# Akustikk_forsterkerkrets.net
KiCad netlist of a schematic drawn in Altium Designer
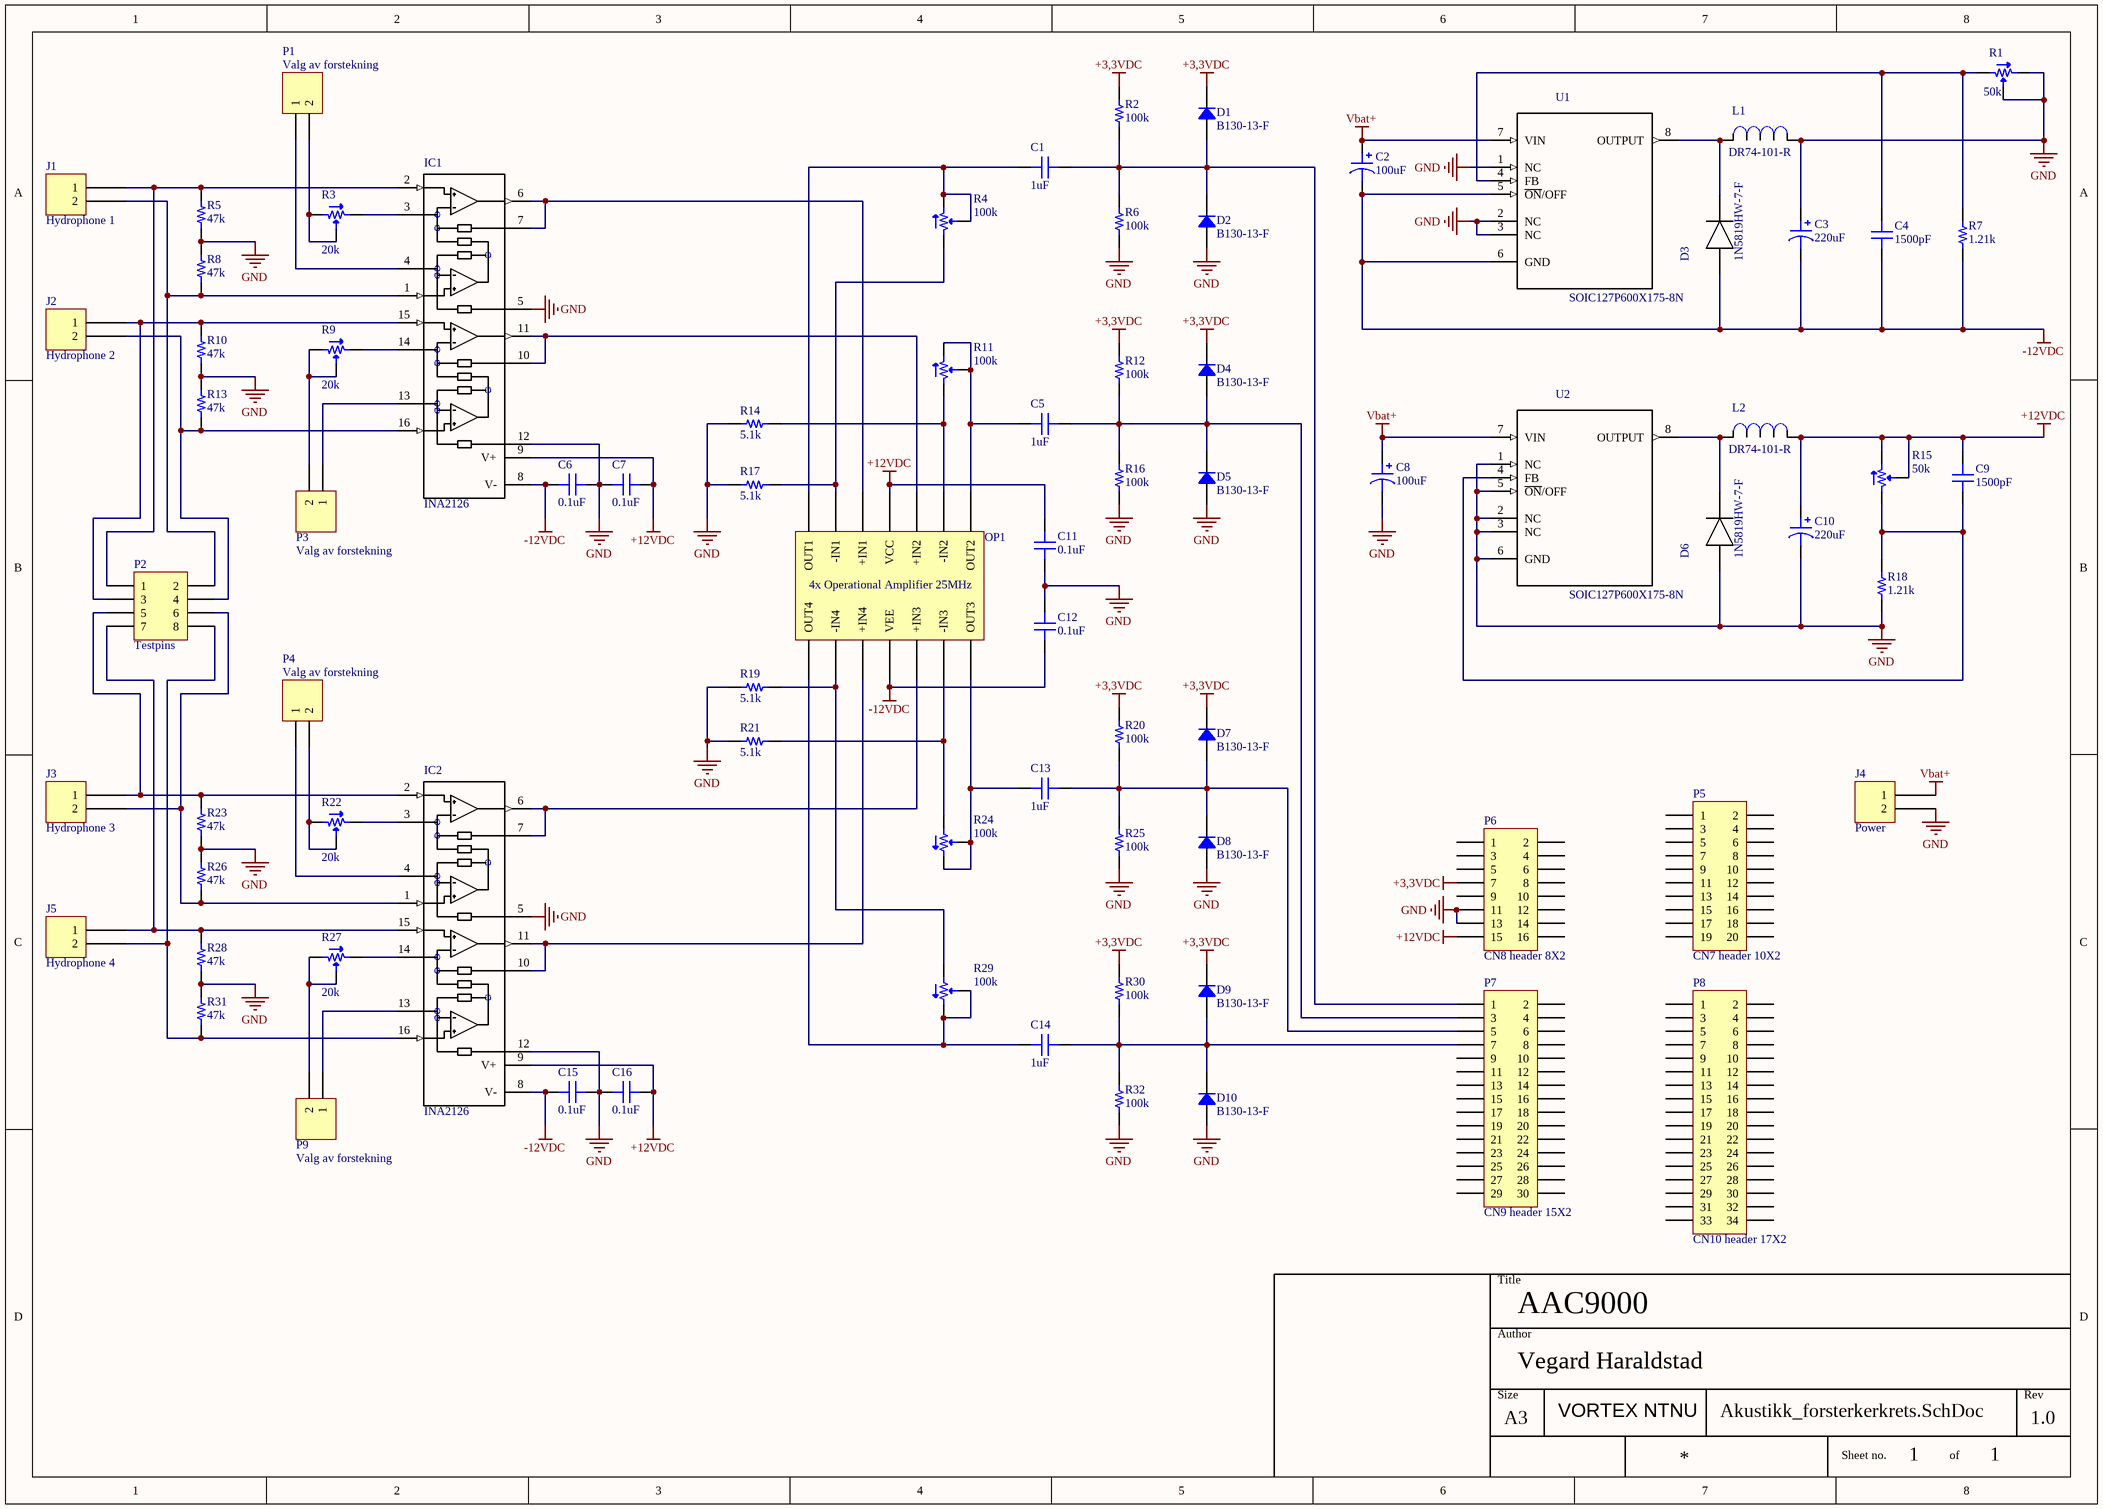
[diagram p0: Akustikk_forsterkerkrets.SchDoc]

(export (version "E")
  (design (tool "Eeschema 10.0.6"))
  (components
    (comp (ref "C1")
      (value "1uF")
      (footprint "CAP 0805/2012")
      (description "CAP CER 1UF 25V X7R 0805")
      (fields (field (name "PART NUMBER") "C0805C105J3RACTU") (field (name "MANUFACTURER") "Kemet"))
      (libsource (lib "Celestial Library Database") (part "Capacitor"))
    )
    (comp (ref "C2")
      (value "100uF")
      (footprint "CAP ALUM 10.3MM")
      (description "CAP ALUM 100UF 20% 50V SMD")
      (fields
        (field (name "PART NUMBER") "EEE-FC1H101P")
        (field (name "MANUFACTURER") "Panasonic Electronic Components")
      )
      (libsource (lib "Celestial Library Database") (part "Polarised Capacitor"))
    )
    (comp (ref "C3")
      (value "220uF")
      (footprint "CAP ALUM 6.6MM")
      (description "CAP ALUM 220UF 20% 25V SMD")
      (fields
        (field (name "PART NUMBER") "EEE-FTE221XAP")
        (field (name "MANUFACTURER") "Panasonic Electronic Components")
      )
      (libsource (lib "Celestial Library Database") (part "Polarised Capacitor"))
    )
    (comp (ref "C4")
      (value "1500pF")
      (footprint "CAP 0805/2012")
      (description "CAP CER 1500PF 50V C0G 0805")
      (fields
        (field (name "PART NUMBER") "C2012C0G1H152J060AA")
        (field (name "MANUFACTURER") "TDK Corporation")
      )
      (libsource (lib "Celestial Library Database") (part "Capacitor"))
    )
    (comp (ref "C5")
      (value "1uF")
      (footprint "CAP 0805/2012")
      (description "CAP CER 1UF 25V X7R 0805")
      (fields (field (name "PART NUMBER") "C0805C105J3RACTU") (field (name "MANUFACTURER") "Kemet"))
      (libsource (lib "Celestial Library Database") (part "Capacitor"))
    )
    (comp (ref "C6")
      (value "0.1uF")
      (footprint "CAP 0805/2012")
      (description "CAP CER 0.1UF 25V X7R 0805")
      (fields
        (field (name "PART NUMBER") "CL21B104KACNNNC")
        (field (name "MANUFACTURER") "Samsung Electro-Mechanics America, Inc.")
      )
      (libsource (lib "Celestial Library Database") (part "Capacitor"))
    )
    (comp (ref "C7")
      (value "0.1uF")
      (footprint "CAP 0805/2012")
      (description "CAP CER 0.1UF 25V X7R 0805")
      (fields
        (field (name "PART NUMBER") "CL21B104KACNNNC")
        (field (name "MANUFACTURER") "Samsung Electro-Mechanics America, Inc.")
      )
      (libsource (lib "Celestial Library Database") (part "Capacitor"))
    )
    (comp (ref "C8")
      (value "100uF")
      (footprint "CAP ALUM 10.3MM")
      (description "CAP ALUM 100UF 20% 50V SMD")
      (fields
        (field (name "PART NUMBER") "EEE-FC1H101P")
        (field (name "MANUFACTURER") "Panasonic Electronic Components")
      )
      (libsource (lib "Celestial Library Database") (part "Polarised Capacitor"))
    )
    (comp (ref "C9")
      (value "1500pF")
      (footprint "CAP 0805/2012")
      (description "CAP CER 1500PF 50V C0G 0805")
      (fields
        (field (name "PART NUMBER") "C2012C0G1H152J060AA")
        (field (name "MANUFACTURER") "TDK Corporation")
      )
      (libsource (lib "Celestial Library Database") (part "Capacitor"))
    )
    (comp (ref "C10")
      (value "220uF")
      (footprint "CAP ALUM 6.6MM")
      (description "CAP ALUM 220UF 20% 25V SMD")
      (fields
        (field (name "PART NUMBER") "EEE-FTE221XAP")
        (field (name "MANUFACTURER") "Panasonic Electronic Components")
      )
      (libsource (lib "Celestial Library Database") (part "Polarised Capacitor"))
    )
    (comp (ref "C11")
      (value "0.1uF")
      (footprint "CAP 0805/2012")
      (description "CAP CER 0.1UF 25V X7R 0805")
      (fields
        (field (name "PART NUMBER") "CL21B104KACNNNC")
        (field (name "MANUFACTURER") "Samsung Electro-Mechanics America, Inc.")
      )
      (libsource (lib "Celestial Library Database") (part "Capacitor"))
    )
    (comp (ref "C12")
      (value "0.1uF")
      (footprint "CAP 0805/2012")
      (description "CAP CER 0.1UF 25V X7R 0805")
      (fields
        (field (name "PART NUMBER") "CL21B104KACNNNC")
        (field (name "MANUFACTURER") "Samsung Electro-Mechanics America, Inc.")
      )
      (libsource (lib "Celestial Library Database") (part "Capacitor"))
    )
    (comp (ref "C13")
      (value "1uF")
      (footprint "CAP 0805/2012")
      (description "CAP CER 1UF 25V X7R 0805")
      (fields (field (name "PART NUMBER") "C0805C105J3RACTU") (field (name "MANUFACTURER") "Kemet"))
      (libsource (lib "Celestial Library Database") (part "Capacitor"))
    )
    (comp (ref "C14")
      (value "1uF")
      (footprint "CAP 0805/2012")
      (description "CAP CER 1UF 25V X7R 0805")
      (fields (field (name "PART NUMBER") "C0805C105J3RACTU") (field (name "MANUFACTURER") "Kemet"))
      (libsource (lib "Celestial Library Database") (part "Capacitor"))
    )
    (comp (ref "C15")
      (value "0.1uF")
      (footprint "CAP 0805/2012")
      (description "CAP CER 0.1UF 25V X7R 0805")
      (fields
        (field (name "PART NUMBER") "CL21B104KACNNNC")
        (field (name "MANUFACTURER") "Samsung Electro-Mechanics America, Inc.")
      )
      (libsource (lib "Celestial Library Database") (part "Capacitor"))
    )
    (comp (ref "C16")
      (value "0.1uF")
      (footprint "CAP 0805/2012")
      (description "CAP CER 0.1UF 25V X7R 0805")
      (fields
        (field (name "PART NUMBER") "CL21B104KACNNNC")
        (field (name "MANUFACTURER") "Samsung Electro-Mechanics America, Inc.")
      )
      (libsource (lib "Celestial Library Database") (part "Capacitor"))
    )
    (comp (ref "D1")
      (value "B130-13-F")
      (footprint "DO214AC SMA")
      (description "DIODE SCHOTTKY 30V 1A SMA")
      (fields (field (name "MANUFACTURER") "Diodes Incorporated"))
      (libsource (lib "Celestial Library Database") (part "Diode"))
    )
    (comp (ref "D2")
      (value "B130-13-F")
      (footprint "DO214AC SMA")
      (description "DIODE SCHOTTKY 30V 1A SMA")
      (fields (field (name "MANUFACTURER") "Diodes Incorporated"))
      (libsource (lib "Celestial Library Database") (part "Diode"))
    )
    (comp (ref "D3")
      (value "1N5819HW-7-F")
      (footprint "1N5819HW-7-F")
      (description "1N5819HW Series 40 V 1 A Surface Mount Schottky Barrier Rectifier - SOD-123")
      (fields (field (name "DIGI-KEY_PART_NUMBER") "1N5819HW-FDICT-ND") (field (name "MF") "Diodes Inc."))
      (libsource (lib "Vortex-component-database") (part "1N5819HW-7-F"))
    )
    (comp (ref "D4")
      (value "B130-13-F")
      (footprint "DO214AC SMA")
      (description "DIODE SCHOTTKY 30V 1A SMA")
      (fields (field (name "MANUFACTURER") "Diodes Incorporated"))
      (libsource (lib "Celestial Library Database") (part "Diode"))
    )
    (comp (ref "D5")
      (value "B130-13-F")
      (footprint "DO214AC SMA")
      (description "DIODE SCHOTTKY 30V 1A SMA")
      (fields (field (name "MANUFACTURER") "Diodes Incorporated"))
      (libsource (lib "Celestial Library Database") (part "Diode"))
    )
    (comp (ref "D6")
      (value "1N5819HW-7-F")
      (footprint "1N5819HW-7-F")
      (description "1N5819HW Series 40 V 1 A Surface Mount Schottky Barrier Rectifier - SOD-123")
      (fields (field (name "DIGI-KEY_PART_NUMBER") "1N5819HW-FDICT-ND") (field (name "MF") "Diodes Inc."))
      (libsource (lib "Vortex-component-database") (part "1N5819HW-7-F"))
    )
    (comp (ref "D7")
      (value "B130-13-F")
      (footprint "DO214AC SMA")
      (description "DIODE SCHOTTKY 30V 1A SMA")
      (fields (field (name "MANUFACTURER") "Diodes Incorporated"))
      (libsource (lib "Celestial Library Database") (part "Diode"))
    )
    (comp (ref "D8")
      (value "B130-13-F")
      (footprint "DO214AC SMA")
      (description "DIODE SCHOTTKY 30V 1A SMA")
      (fields (field (name "MANUFACTURER") "Diodes Incorporated"))
      (libsource (lib "Celestial Library Database") (part "Diode"))
    )
    (comp (ref "D9")
      (value "B130-13-F")
      (footprint "DO214AC SMA")
      (description "DIODE SCHOTTKY 30V 1A SMA")
      (fields (field (name "MANUFACTURER") "Diodes Incorporated"))
      (libsource (lib "Celestial Library Database") (part "Diode"))
    )
    (comp (ref "D10")
      (value "B130-13-F")
      (footprint "DO214AC SMA")
      (description "DIODE SCHOTTKY 30V 1A SMA")
      (fields (field (name "MANUFACTURER") "Diodes Incorporated"))
      (libsource (lib "Celestial Library Database") (part "Diode"))
    )
    (comp (ref "IC1")
      (value "INA2126")
      (footprint "SOP63P600X175-16N")
      (fields (field (name "MF") "Texas Instruments") (field (name "PART NUMBER") "INA2126EA/250"))
      (libsource (lib "Vortex-component-database") (part "INA2126"))
    )
    (comp (ref "IC2")
      (value "INA2126")
      (footprint "SOP63P600X175-16N")
      (fields (field (name "MF") "Texas Instruments") (field (name "PART NUMBER") "INA2126EA/250"))
      (libsource (lib "Vortex-component-database") (part "INA2126"))
    )
    (comp (ref "J1")
      (value "Hydrophone 1")
      (footprint "JST XH B2B-XH-A")
      (description "CONN HEADER XH TOP 2POS 2.5MM")
      (fields
        (field (name "PART NUMBER") "B2B-XH-A(LF)(SN)")
        (field (name "MANUFACTURER") "JST Sales America Inc.")
      )
      (libsource (lib "Celestial Library Database") (part "2 Pin"))
    )
    (comp (ref "J2")
      (value "Hydrophone 2")
      (footprint "JST XH B2B-XH-A")
      (description "CONN HEADER XH TOP 2POS 2.5MM")
      (fields
        (field (name "PART NUMBER") "B2B-XH-A(LF)(SN)")
        (field (name "MANUFACTURER") "JST Sales America Inc.")
      )
      (libsource (lib "Celestial Library Database") (part "2 Pin"))
    )
    (comp (ref "J3")
      (value "Hydrophone 3")
      (footprint "JST XH B2B-XH-A")
      (description "CONN HEADER XH TOP 2POS 2.5MM")
      (fields
        (field (name "PART NUMBER") "B2B-XH-A(LF)(SN)")
        (field (name "MANUFACTURER") "JST Sales America Inc.")
      )
      (libsource (lib "Celestial Library Database") (part "2 Pin"))
    )
    (comp (ref "J4")
      (value "Power")
      (footprint "JST XH B2B-XH-A")
      (description "CONN HEADER XH TOP 2POS 2.5MM")
      (fields
        (field (name "PART NUMBER") "B2B-XH-A(LF)(SN)")
        (field (name "MANUFACTURER") "JST Sales America Inc.")
      )
      (libsource (lib "Celestial Library Database") (part "2 Pin"))
    )
    (comp (ref "J5")
      (value "Hydrophone 4")
      (footprint "JST XH B2B-XH-A")
      (description "CONN HEADER XH TOP 2POS 2.5MM")
      (fields
        (field (name "PART NUMBER") "B2B-XH-A(LF)(SN)")
        (field (name "MANUFACTURER") "JST Sales America Inc.")
      )
      (libsource (lib "Celestial Library Database") (part "2 Pin"))
    )
    (comp (ref "L1")
      (value "DR74-101-R")
      (footprint "DR74-101-R")
      (description "Inductor Power Shielded Drum Core 101.6uH/100uH 20% 100KHz Ferrite 860mA 383mOhm DCR T/R")
      (fields (field (name "MF") "Eaton"))
      (libsource (lib "Vortex-component-database") (part "DR74-101-R"))
    )
    (comp (ref "L2")
      (value "DR74-101-R")
      (footprint "DR74-101-R")
      (description "Inductor Power Shielded Drum Core 101.6uH/100uH 20% 100KHz Ferrite 860mA 383mOhm DCR T/R")
      (fields (field (name "MF") "Eaton"))
      (libsource (lib "Vortex-component-database") (part "DR74-101-R"))
    )
    (comp (ref "OP1")
      (value "4x Operational Amplifier 25MHz")
      (footprint "SOIC127P600X175-14N")
      (fields (field (name "PART NUMBER") "LM837MX/NOPB"))
      (libsource (lib "Vortex-component-database") (part "LM837MX/NOPB"))
    )
    (comp (ref "P1")
      (value "Valg av forstekning")
      (footprint "HDR1X2")
      (description "Header, 2-Pin")
      (fields (field (name "PUBLISHER") "Altium Limited"))
      (libsource (lib "") (part "Header 2_1"))
    )
    (comp (ref "P2")
      (value "Testpins")
      (footprint "HDR2X4")
      (description "Header, 4-Pin, Dual row")
      (fields (field (name "PUBLISHER") "Altium Limited"))
      (libsource (lib "Miscellaneous Connectors") (part "Header 4X2"))
    )
    (comp (ref "P3")
      (value "Valg av forstekning")
      (footprint "HDR1X2")
      (description "Header, 2-Pin")
      (fields (field (name "PUBLISHER") "Altium Limited"))
      (libsource (lib "Miscellaneous Connectors") (part "Header 2"))
    )
    (comp (ref "P4")
      (value "Valg av forstekning")
      (footprint "HDR1X2")
      (description "Header, 2-Pin")
      (fields (field (name "PUBLISHER") "Altium Limited"))
      (libsource (lib "") (part "Header 2_1"))
    )
    (comp (ref "P5")
      (value "CN7 header 10X2")
      (footprint "HDR2X10")
      (description "Header, 10-Pin, Dual row")
      (fields (field (name "PUBLISHER") "Altium Limited"))
      (libsource (lib "Miscellaneous Connectors") (part "Header 10X2"))
    )
    (comp (ref "P6")
      (value "CN8 header 8X2")
      (footprint "HDR2X8")
      (description "Header, 8-Pin, Dual row")
      (fields (field (name "PUBLISHER") "Altium Limited"))
      (libsource (lib "Miscellaneous Connectors") (part "Header 8X2"))
    )
    (comp (ref "P7")
      (value "CN9 header 15X2")
      (footprint "HDR2X15")
      (description "Header, 15-Pin, Dual row")
      (fields (field (name "PUBLISHER") "Altium Limited"))
      (libsource (lib "Miscellaneous Connectors") (part "Header 15X2"))
    )
    (comp (ref "P8")
      (value "CN10 header 17X2")
      (footprint "HDR2X17")
      (description "Header, 17-Pin, Dual row")
      (fields (field (name "PUBLISHER") "Altium Limited"))
      (libsource (lib "Miscellaneous Connectors") (part "Header 17X2"))
    )
    (comp (ref "P9")
      (value "Valg av forstekning")
      (footprint "HDR1X2")
      (description "Header, 2-Pin")
      (fields (field (name "PUBLISHER") "Altium Limited"))
      (libsource (lib "Miscellaneous Connectors") (part "Header 2"))
    )
    (comp (ref "R1")
      (value "50k")
      (footprint "POT BOURNS TRIMPOT 3302")
      (description "TRIMMER 20K OHM 0.15W SMD")
      (fields (field (name "PART NUMBER") "3302W-3-203E") (field (name "MANUFACTURER") "Bourns Inc."))
      (libsource (lib "Celestial Library Database") (part "Potentiometer"))
    )
    (comp (ref "R2")
      (value "100k")
      (footprint "RES 0805/2012")
      (description "RES SMD 100K OHM 5% 1/8W 0805")
      (fields
        (field (name "PART NUMBER") "ERJ-6GEYJ104V")
        (field (name "MANUFACTURER") "Panasonic Electronic Components")
      )
      (libsource (lib "Celestial Library Database") (part "Resistor"))
    )
    (comp (ref "R3")
      (value "20k")
      (footprint "POT BOURNS TRIMPOT 3302")
      (description "TRIMMER 20K OHM 0.15W SMD")
      (fields (field (name "PART NUMBER") "3302W-3-203E") (field (name "MANUFACTURER") "Bourns Inc."))
      (libsource (lib "Celestial Library Database") (part "Potentiometer"))
    )
    (comp (ref "R4")
      (value "100k")
      (footprint "POT BOURNS TRIMPOT 3302")
      (description "TRIMMER 20K OHM 0.15W SMD")
      (fields (field (name "PART NUMBER") "3302W-3-203E") (field (name "MANUFACTURER") "Bourns Inc."))
      (libsource (lib "Celestial Library Database") (part "Potentiometer"))
    )
    (comp (ref "R5")
      (value "47k")
      (footprint "RES 0805/2012")
      (description "RES SMD 47K OHM 1% 1/8W 0805")
      (fields
        (field (name "PART NUMBER") "ERJ-6ENF4702V")
        (field (name "MANUFACTURER") "Panasonic Electronic Components")
      )
      (libsource (lib "Celestial Library Database") (part "Resistor"))
    )
    (comp (ref "R6")
      (value "100k")
      (footprint "RES 0805/2012")
      (description "RES SMD 100K OHM 5% 1/8W 0805")
      (fields
        (field (name "PART NUMBER") "ERJ-6GEYJ104V")
        (field (name "MANUFACTURER") "Panasonic Electronic Components")
      )
      (libsource (lib "Celestial Library Database") (part "Resistor"))
    )
    (comp (ref "R7")
      (value "1.21k")
      (footprint "RES 0805/2012")
      (description "RES SMD 1.21K OHM 0.1% 1/8W 0805")
      (fields
        (field (name "PART NUMBER") "ERA-6AEB1211V")
        (field (name "MANUFACTURER") "Panasonic Electronic Components")
      )
      (libsource (lib "Celestial Library Database") (part "Resistor"))
    )
    (comp (ref "R8")
      (value "47k")
      (footprint "RES 0805/2012")
      (description "RES SMD 47K OHM 1% 1/8W 0805")
      (fields
        (field (name "PART NUMBER") "ERJ-6ENF4702V")
        (field (name "MANUFACTURER") "Panasonic Electronic Components")
      )
      (libsource (lib "Celestial Library Database") (part "Resistor"))
    )
    (comp (ref "R9")
      (value "20k")
      (footprint "POT BOURNS TRIMPOT 3302")
      (description "TRIMMER 20K OHM 0.15W SMD")
      (fields (field (name "PART NUMBER") "3302W-3-203E") (field (name "MANUFACTURER") "Bourns Inc."))
      (libsource (lib "Celestial Library Database") (part "Potentiometer"))
    )
    (comp (ref "R10")
      (value "47k")
      (footprint "RES 0805/2012")
      (description "RES SMD 47K OHM 1% 1/8W 0805")
      (fields
        (field (name "PART NUMBER") "ERJ-6ENF4702V")
        (field (name "MANUFACTURER") "Panasonic Electronic Components")
      )
      (libsource (lib "Celestial Library Database") (part "Resistor"))
    )
    (comp (ref "R11")
      (value "100k")
      (footprint "POT BOURNS TRIMPOT 3302")
      (description "TRIMMER 20K OHM 0.15W SMD")
      (fields (field (name "PART NUMBER") "3302W-3-203E") (field (name "MANUFACTURER") "Bourns Inc."))
      (libsource (lib "Celestial Library Database") (part "Potentiometer"))
    )
    (comp (ref "R12")
      (value "100k")
      (footprint "RES 0805/2012")
      (description "RES SMD 100K OHM 5% 1/8W 0805")
      (fields
        (field (name "PART NUMBER") "ERJ-6GEYJ104V")
        (field (name "MANUFACTURER") "Panasonic Electronic Components")
      )
      (libsource (lib "Celestial Library Database") (part "Resistor"))
    )
    (comp (ref "R13")
      (value "47k")
      (footprint "RES 0805/2012")
      (description "RES SMD 47K OHM 1% 1/8W 0805")
      (fields
        (field (name "PART NUMBER") "ERJ-6ENF4702V")
        (field (name "MANUFACTURER") "Panasonic Electronic Components")
      )
      (libsource (lib "Celestial Library Database") (part "Resistor"))
    )
    (comp (ref "R14")
      (value "5.1k")
      (footprint "RES 0805/2012")
      (description "RES SMD 5.1K OHM 1% 1/8W 0805")
      (fields
        (field (name "PART NUMBER") "ERJ-6ENF5101V")
        (field (name "MANUFACTURER") "Panasonic Electronic Components")
      )
      (libsource (lib "Celestial Library Database") (part "Resistor"))
    )
    (comp (ref "R15")
      (value "50k")
      (footprint "POT BOURNS TRIMPOT 3302")
      (description "TRIMMER 20K OHM 0.15W SMD")
      (fields (field (name "PART NUMBER") "3302W-3-203E") (field (name "MANUFACTURER") "Bourns Inc."))
      (libsource (lib "Celestial Library Database") (part "Potentiometer"))
    )
    (comp (ref "R16")
      (value "100k")
      (footprint "RES 0805/2012")
      (description "RES SMD 100K OHM 5% 1/8W 0805")
      (fields
        (field (name "PART NUMBER") "ERJ-6GEYJ104V")
        (field (name "MANUFACTURER") "Panasonic Electronic Components")
      )
      (libsource (lib "Celestial Library Database") (part "Resistor"))
    )
    (comp (ref "R17")
      (value "5.1k")
      (footprint "RES 0805/2012")
      (description "RES SMD 5.1K OHM 1% 1/8W 0805")
      (fields
        (field (name "PART NUMBER") "ERJ-6ENF5101V")
        (field (name "MANUFACTURER") "Panasonic Electronic Components")
      )
      (libsource (lib "Celestial Library Database") (part "Resistor"))
    )
    (comp (ref "R18")
      (value "1.21k")
      (footprint "RES 0805/2012")
      (description "RES SMD 1.21K OHM 0.1% 1/8W 0805")
      (fields
        (field (name "PART NUMBER") "ERA-6AEB1211V")
        (field (name "MANUFACTURER") "Panasonic Electronic Components")
      )
      (libsource (lib "Celestial Library Database") (part "Resistor"))
    )
    (comp (ref "R19")
      (value "5.1k")
      (footprint "RES 0805/2012")
      (description "RES SMD 5.1K OHM 1% 1/8W 0805")
      (fields
        (field (name "PART NUMBER") "ERJ-6ENF5101V")
        (field (name "MANUFACTURER") "Panasonic Electronic Components")
      )
      (libsource (lib "Celestial Library Database") (part "Resistor"))
    )
    (comp (ref "R20")
      (value "100k")
      (footprint "RES 0805/2012")
      (description "RES SMD 100K OHM 5% 1/8W 0805")
      (fields
        (field (name "PART NUMBER") "ERJ-6GEYJ104V")
        (field (name "MANUFACTURER") "Panasonic Electronic Components")
      )
      (libsource (lib "Celestial Library Database") (part "Resistor"))
    )
    (comp (ref "R21")
      (value "5.1k")
      (footprint "RES 0805/2012")
      (description "RES SMD 5.1K OHM 1% 1/8W 0805")
      (fields
        (field (name "PART NUMBER") "ERJ-6ENF5101V")
        (field (name "MANUFACTURER") "Panasonic Electronic Components")
      )
      (libsource (lib "Celestial Library Database") (part "Resistor"))
    )
    (comp (ref "R22")
      (value "20k")
      (footprint "POT BOURNS TRIMPOT 3302")
      (description "TRIMMER 20K OHM 0.15W SMD")
      (fields (field (name "PART NUMBER") "3302W-3-203E") (field (name "MANUFACTURER") "Bourns Inc."))
      (libsource (lib "Celestial Library Database") (part "Potentiometer"))
    )
    (comp (ref "R23")
      (value "47k")
      (footprint "RES 0805/2012")
      (description "RES SMD 47K OHM 1% 1/8W 0805")
      (fields
        (field (name "PART NUMBER") "ERJ-6ENF4702V")
        (field (name "MANUFACTURER") "Panasonic Electronic Components")
      )
      (libsource (lib "Celestial Library Database") (part "Resistor"))
    )
    (comp (ref "R24")
      (value "100k")
      (footprint "POT BOURNS TRIMPOT 3302")
      (description "TRIMMER 20K OHM 0.15W SMD")
      (fields (field (name "PART NUMBER") "3302W-3-203E") (field (name "MANUFACTURER") "Bourns Inc."))
      (libsource (lib "Celestial Library Database") (part "Potentiometer"))
    )
    (comp (ref "R25")
      (value "100k")
      (footprint "RES 0805/2012")
      (description "RES SMD 100K OHM 5% 1/8W 0805")
      (fields
        (field (name "PART NUMBER") "ERJ-6GEYJ104V")
        (field (name "MANUFACTURER") "Panasonic Electronic Components")
      )
      (libsource (lib "Celestial Library Database") (part "Resistor"))
    )
    (comp (ref "R26")
      (value "47k")
      (footprint "RES 0805/2012")
      (description "RES SMD 47K OHM 1% 1/8W 0805")
      (fields
        (field (name "PART NUMBER") "ERJ-6ENF4702V")
        (field (name "MANUFACTURER") "Panasonic Electronic Components")
      )
      (libsource (lib "Celestial Library Database") (part "Resistor"))
    )
    (comp (ref "R27")
      (value "20k")
      (footprint "POT BOURNS TRIMPOT 3302")
      (description "TRIMMER 20K OHM 0.15W SMD")
      (fields (field (name "PART NUMBER") "3302W-3-203E") (field (name "MANUFACTURER") "Bourns Inc."))
      (libsource (lib "Celestial Library Database") (part "Potentiometer"))
    )
    (comp (ref "R28")
      (value "47k")
      (footprint "RES 0805/2012")
      (description "RES SMD 47K OHM 1% 1/8W 0805")
      (fields
        (field (name "PART NUMBER") "ERJ-6ENF4702V")
        (field (name "MANUFACTURER") "Panasonic Electronic Components")
      )
      (libsource (lib "Celestial Library Database") (part "Resistor"))
    )
    (comp (ref "R29")
      (value "100k")
      (footprint "POT BOURNS TRIMPOT 3302")
      (description "TRIMMER 20K OHM 0.15W SMD")
      (fields (field (name "PART NUMBER") "3302W-3-203E") (field (name "MANUFACTURER") "Bourns Inc."))
      (libsource (lib "Celestial Library Database") (part "Potentiometer"))
    )
    (comp (ref "R30")
      (value "100k")
      (footprint "RES 0805/2012")
      (description "RES SMD 100K OHM 5% 1/8W 0805")
      (fields
        (field (name "PART NUMBER") "ERJ-6GEYJ104V")
        (field (name "MANUFACTURER") "Panasonic Electronic Components")
      )
      (libsource (lib "Celestial Library Database") (part "Resistor"))
    )
    (comp (ref "R31")
      (value "47k")
      (footprint "RES 0805/2012")
      (description "RES SMD 47K OHM 1% 1/8W 0805")
      (fields
        (field (name "PART NUMBER") "ERJ-6ENF4702V")
        (field (name "MANUFACTURER") "Panasonic Electronic Components")
      )
      (libsource (lib "Celestial Library Database") (part "Resistor"))
    )
    (comp (ref "R32")
      (value "100k")
      (footprint "RES 0805/2012")
      (description "RES SMD 100K OHM 5% 1/8W 0805")
      (fields
        (field (name "PART NUMBER") "ERJ-6GEYJ104V")
        (field (name "MANUFACTURER") "Panasonic Electronic Components")
      )
      (libsource (lib "Celestial Library Database") (part "Resistor"))
    )
    (comp (ref "U1")
      (value "SOIC127P600X175-8N")
      (footprint "SOIC127P600X175-8N")
      (description "SIMPLE SWITCHERÂ® 40V, 500mA Low Component Count Step-Down Regulator 8-SOIC -40 to 125")
      (fields (field (name "MP") "LM2674MX-12/NOPB") (field (name "MF") "Texas Instruments"))
      (libsource (lib "Vortex-component-database") (part "SOIC127P600X175-8N"))
    )
    (comp (ref "U2")
      (value "SOIC127P600X175-8N")
      (footprint "SOIC127P600X175-8N")
      (description "SIMPLE SWITCHERÂ® 40V, 500mA Low Component Count Step-Down Regulator 8-SOIC -40 to 125")
      (fields (field (name "MP") "LM2674MX-12/NOPB") (field (name "MF") "Texas Instruments"))
      (libsource (lib "Vortex-component-database") (part "SOIC127P600X175-8N"))
    )
  )
  (nets
    (net (code "1") (name "+3,3VDC") (class "Default")
      (node (ref "D1") (pin "2") (pinfunction "2_2") (pintype "passive"))
      (node (ref "D4") (pin "2") (pinfunction "2_2") (pintype "passive"))
      (node (ref "D7") (pin "2") (pinfunction "2_2") (pintype "passive"))
      (node (ref "D9") (pin "2") (pinfunction "2_2") (pintype "passive"))
      (node (ref "P6") (pin "7") (pinfunction "7_7") (pintype "passive"))
      (node (ref "R12") (pin "2") (pinfunction "2_2") (pintype "passive"))
      (node (ref "R2") (pin "2") (pinfunction "2_2") (pintype "passive"))
      (node (ref "R20") (pin "2") (pinfunction "2_2") (pintype "passive"))
      (node (ref "R30") (pin "2") (pinfunction "2_2") (pintype "passive"))
    )
    (net (code "2") (name "+12VDC") (class "Default")
      (node (ref "C10") (pin "1") (pinfunction "1_1") (pintype "passive"))
      (node (ref "C11") (pin "2") (pinfunction "2_2") (pintype "passive"))
      (node (ref "C16") (pin "2") (pinfunction "2_2") (pintype "passive"))
      (node (ref "C7") (pin "2") (pinfunction "2_2") (pintype "passive"))
      (node (ref "C9") (pin "2") (pinfunction "2_2") (pintype "passive"))
      (node (ref "IC1") (pin "9") (pinfunction "V+_9") (pintype "power_in"))
      (node (ref "IC2") (pin "9") (pinfunction "V+_9") (pintype "power_in"))
      (node (ref "L2") (pin "1") (pinfunction "1_1") (pintype "passive"))
      (node (ref "OP1") (pin "4") (pinfunction "VCC_4") (pintype "passive"))
      (node (ref "P6") (pin "15") (pinfunction "15_15") (pintype "passive"))
      (node (ref "R15") (pin "2") (pinfunction "2_2") (pintype "passive"))
      (node (ref "R15") (pin "3") (pinfunction "3_3") (pintype "passive"))
    )
    (net (code "3") (name "-12VDC") (class "Default")
      (node (ref "C12") (pin "1") (pinfunction "1_1") (pintype "passive"))
      (node (ref "C15") (pin "1") (pinfunction "1_1") (pintype "passive"))
      (node (ref "C2") (pin "2") (pinfunction "2_2") (pintype "passive"))
      (node (ref "C3") (pin "2") (pinfunction "2_2") (pintype "passive"))
      (node (ref "C4") (pin "1") (pinfunction "1_1") (pintype "passive"))
      (node (ref "C6") (pin "1") (pinfunction "1_1") (pintype "passive"))
      (node (ref "D3") (pin "2") (pinfunction "A_2") (pintype "passive"))
      (node (ref "IC1") (pin "8") (pinfunction "V-_8") (pintype "power_in"))
      (node (ref "IC2") (pin "8") (pinfunction "V-_8") (pintype "power_in"))
      (node (ref "OP1") (pin "11") (pinfunction "VEE_11") (pintype "passive"))
      (node (ref "R7") (pin "1") (pinfunction "1_1") (pintype "passive"))
      (node (ref "U1") (pin "5") (pinfunction "~{ON}/OFF_5") (pintype "input"))
      (node (ref "U1") (pin "6") (pinfunction "GND_6") (pintype "passive"))
    )
    (net (code "4") (name "GND") (class "Default")
      (node (ref "C10") (pin "2") (pinfunction "2_2") (pintype "passive"))
      (node (ref "C11") (pin "1") (pinfunction "1_1") (pintype "passive"))
      (node (ref "C12") (pin "2") (pinfunction "2_2") (pintype "passive"))
      (node (ref "C15") (pin "2") (pinfunction "2_2") (pintype "passive"))
      (node (ref "C16") (pin "1") (pinfunction "1_1") (pintype "passive"))
      (node (ref "C3") (pin "1") (pinfunction "1_1") (pintype "passive"))
      (node (ref "C6") (pin "2") (pinfunction "2_2") (pintype "passive"))
      (node (ref "C7") (pin "1") (pinfunction "1_1") (pintype "passive"))
      (node (ref "C8") (pin "2") (pinfunction "2_2") (pintype "passive"))
      (node (ref "D10") (pin "1") (pinfunction "1_1") (pintype "passive"))
      (node (ref "D2") (pin "1") (pinfunction "1_1") (pintype "passive"))
      (node (ref "D5") (pin "1") (pinfunction "1_1") (pintype "passive"))
      (node (ref "D6") (pin "2") (pinfunction "A_2") (pintype "passive"))
      (node (ref "D8") (pin "1") (pinfunction "1_1") (pintype "passive"))
      (node (ref "IC1") (pin "12") (pinfunction "REFB_12") (pintype "power_in"))
      (node (ref "IC1") (pin "5") (pinfunction "REFA_5") (pintype "power_in"))
      (node (ref "IC2") (pin "12") (pinfunction "REFB_12") (pintype "power_in"))
      (node (ref "IC2") (pin "5") (pinfunction "REFA_5") (pintype "power_in"))
      (node (ref "J4") (pin "2") (pinfunction "2_2") (pintype "passive"))
      (node (ref "L1") (pin "1") (pinfunction "1_1") (pintype "passive"))
      (node (ref "P6") (pin "11") (pinfunction "11_11") (pintype "passive"))
      (node (ref "P6") (pin "13") (pinfunction "13_13") (pintype "passive"))
      (node (ref "R1") (pin "2") (pinfunction "2_2") (pintype "passive"))
      (node (ref "R1") (pin "3") (pinfunction "3_3") (pintype "passive"))
      (node (ref "R10") (pin "1") (pinfunction "1_1") (pintype "passive"))
      (node (ref "R13") (pin "2") (pinfunction "2_2") (pintype "passive"))
      (node (ref "R14") (pin "2") (pinfunction "2_2") (pintype "passive"))
      (node (ref "R16") (pin "1") (pinfunction "1_1") (pintype "passive"))
      (node (ref "R17") (pin "2") (pinfunction "2_2") (pintype "passive"))
      (node (ref "R18") (pin "1") (pinfunction "1_1") (pintype "passive"))
      (node (ref "R19") (pin "2") (pinfunction "2_2") (pintype "passive"))
      (node (ref "R21") (pin "2") (pinfunction "2_2") (pintype "passive"))
      (node (ref "R23") (pin "1") (pinfunction "1_1") (pintype "passive"))
      (node (ref "R25") (pin "1") (pinfunction "1_1") (pintype "passive"))
      (node (ref "R26") (pin "2") (pinfunction "2_2") (pintype "passive"))
      (node (ref "R28") (pin "1") (pinfunction "1_1") (pintype "passive"))
      (node (ref "R31") (pin "2") (pinfunction "2_2") (pintype "passive"))
      (node (ref "R32") (pin "1") (pinfunction "1_1") (pintype "passive"))
      (node (ref "R5") (pin "1") (pinfunction "1_1") (pintype "passive"))
      (node (ref "R6") (pin "1") (pinfunction "1_1") (pintype "passive"))
      (node (ref "R8") (pin "2") (pinfunction "2_2") (pintype "passive"))
      (node (ref "U1") (pin "1") (pinfunction "NC_1") (pintype "input"))
      (node (ref "U1") (pin "2") (pinfunction "NC_2") (pintype "passive"))
      (node (ref "U1") (pin "3") (pinfunction "NC_3") (pintype "passive"))
      (node (ref "U2") (pin "1") (pinfunction "NC_1") (pintype "input"))
      (node (ref "U2") (pin "2") (pinfunction "NC_2") (pintype "passive"))
      (node (ref "U2") (pin "3") (pinfunction "NC_3") (pintype "passive"))
      (node (ref "U2") (pin "5") (pinfunction "~{ON}/OFF_5") (pintype "input"))
      (node (ref "U2") (pin "6") (pinfunction "GND_6") (pintype "passive"))
    )
    (net (code "5") (name "Net-(C1-Pad2)") (class "Default")
      (node (ref "C1") (pin "2") (pinfunction "2_2") (pintype "passive"))
      (node (ref "D1") (pin "1") (pinfunction "1_1") (pintype "passive"))
      (node (ref "D2") (pin "2") (pinfunction "2_2") (pintype "passive"))
      (node (ref "P7") (pin "1") (pinfunction "1_1") (pintype "passive"))
      (node (ref "R2") (pin "1") (pinfunction "1_1") (pintype "passive"))
      (node (ref "R6") (pin "2") (pinfunction "2_2") (pintype "passive"))
    )
    (net (code "6") (name "Net-(C5-Pad2)") (class "Default")
      (node (ref "C5") (pin "2") (pinfunction "2_2") (pintype "passive"))
      (node (ref "D4") (pin "1") (pinfunction "1_1") (pintype "passive"))
      (node (ref "D5") (pin "2") (pinfunction "2_2") (pintype "passive"))
      (node (ref "P7") (pin "3") (pinfunction "3_3") (pintype "passive"))
      (node (ref "R12") (pin "1") (pinfunction "1_1") (pintype "passive"))
      (node (ref "R16") (pin "2") (pinfunction "2_2") (pintype "passive"))
    )
    (net (code "7") (name "Net-(C13-Pad2)") (class "Default")
      (node (ref "C13") (pin "2") (pinfunction "2_2") (pintype "passive"))
      (node (ref "D7") (pin "1") (pinfunction "1_1") (pintype "passive"))
      (node (ref "D8") (pin "2") (pinfunction "2_2") (pintype "passive"))
      (node (ref "P7") (pin "5") (pinfunction "5_5") (pintype "passive"))
      (node (ref "R20") (pin "1") (pinfunction "1_1") (pintype "passive"))
      (node (ref "R25") (pin "2") (pinfunction "2_2") (pintype "passive"))
    )
    (net (code "8") (name "Net-(C14-Pad2)") (class "Default")
      (node (ref "C14") (pin "2") (pinfunction "2_2") (pintype "passive"))
      (node (ref "D10") (pin "2") (pinfunction "2_2") (pintype "passive"))
      (node (ref "D9") (pin "1") (pinfunction "1_1") (pintype "passive"))
      (node (ref "P7") (pin "7") (pinfunction "7_7") (pintype "passive"))
      (node (ref "R30") (pin "1") (pinfunction "1_1") (pintype "passive"))
      (node (ref "R32") (pin "2") (pinfunction "2_2") (pintype "passive"))
    )
    (net (code "9") (name "Net-(D3-C)") (class "Default")
      (node (ref "D3") (pin "1") (pinfunction "C_1") (pintype "passive"))
      (node (ref "L1") (pin "2") (pinfunction "2_2") (pintype "passive"))
      (node (ref "U1") (pin "8") (pinfunction "OUTPUT_8") (pintype "output"))
    )
    (net (code "10") (name "Net-(D6-C)") (class "Default")
      (node (ref "D6") (pin "1") (pinfunction "C_1") (pintype "passive"))
      (node (ref "L2") (pin "2") (pinfunction "2_2") (pintype "passive"))
      (node (ref "U2") (pin "8") (pinfunction "OUTPUT_8") (pintype "output"))
    )
    (net (code "11") (name "Net-(IC1-+INA)") (class "Default")
      (node (ref "IC1") (pin "2") (pinfunction "+INA_2") (pintype "input"))
      (node (ref "J1") (pin "1") (pinfunction "1_1") (pintype "passive"))
      (node (ref "P2") (pin "1") (pinfunction "1_1") (pintype "passive"))
      (node (ref "R5") (pin "2") (pinfunction "2_2") (pintype "passive"))
    )
    (net (code "12") (name "Net-(IC1-+INB)") (class "Default")
      (node (ref "IC1") (pin "15") (pinfunction "+INB_15") (pintype "input"))
      (node (ref "J2") (pin "1") (pinfunction "1_1") (pintype "passive"))
      (node (ref "P2") (pin "3") (pinfunction "3_3") (pintype "passive"))
      (node (ref "R10") (pin "2") (pinfunction "2_2") (pintype "passive"))
    )
    (net (code "13") (name "Net-(IC1--INA)") (class "Default")
      (node (ref "IC1") (pin "1") (pinfunction "-INA_1") (pintype "input"))
      (node (ref "J1") (pin "2") (pinfunction "2_2") (pintype "passive"))
      (node (ref "P2") (pin "2") (pinfunction "2_2") (pintype "passive"))
      (node (ref "R8") (pin "1") (pinfunction "1_1") (pintype "passive"))
    )
    (net (code "14") (name "Net-(IC1--INB)") (class "Default")
      (node (ref "IC1") (pin "16") (pinfunction "-INB_16") (pintype "input"))
      (node (ref "J2") (pin "2") (pinfunction "2_2") (pintype "passive"))
      (node (ref "P2") (pin "4") (pinfunction "4_4") (pintype "passive"))
      (node (ref "R13") (pin "1") (pinfunction "1_1") (pintype "passive"))
    )
    (net (code "15") (name "Net-(IC1-OUTA)") (class "Default")
      (node (ref "IC1") (pin "6") (pinfunction "OUTA_6") (pintype "output"))
      (node (ref "IC1") (pin "7") (pinfunction "SENSEA_7") (pintype "passive"))
      (node (ref "OP1") (pin "3") (pinfunction "+IN1_3") (pintype "passive"))
    )
    (net (code "16") (name "Net-(IC1-OUTB)") (class "Default")
      (node (ref "IC1") (pin "10") (pinfunction "SENSEB_10") (pintype "passive"))
      (node (ref "IC1") (pin "11") (pinfunction "OUTB_11") (pintype "output"))
      (node (ref "OP1") (pin "5") (pinfunction "+IN2_5") (pintype "passive"))
    )
    (net (code "17") (name "Net-(IC1-RGA)") (class "Default")
      (node (ref "IC1") (pin "3") (pinfunction "RGA_3") (pintype "passive"))
      (node (ref "R3") (pin "3") (pinfunction "3_3") (pintype "passive"))
    )
    (net (code "18") (name "Net-(IC1-RGA@1)") (class "Default")
      (node (ref "IC1") (pin "4") (pinfunction "RGA@1_4") (pintype "passive"))
      (node (ref "P1") (pin "1") (pinfunction "1_1") (pintype "passive"))
    )
    (net (code "19") (name "Net-(IC1-RGB)") (class "Default")
      (node (ref "IC1") (pin "14") (pinfunction "RGB_14") (pintype "passive"))
      (node (ref "R9") (pin "3") (pinfunction "3_3") (pintype "passive"))
    )
    (net (code "20") (name "Net-(IC1-RGB@1)") (class "Default")
      (node (ref "IC1") (pin "13") (pinfunction "RGB@1_13") (pintype "passive"))
      (node (ref "P3") (pin "1") (pinfunction "1_1") (pintype "passive"))
    )
    (net (code "21") (name "Net-(IC2-+INA)") (class "Default")
      (node (ref "IC2") (pin "2") (pinfunction "+INA_2") (pintype "input"))
      (node (ref "J3") (pin "1") (pinfunction "1_1") (pintype "passive"))
      (node (ref "P2") (pin "5") (pinfunction "5_5") (pintype "passive"))
      (node (ref "R23") (pin "2") (pinfunction "2_2") (pintype "passive"))
    )
    (net (code "22") (name "Net-(IC2-+INB)") (class "Default")
      (node (ref "IC2") (pin "15") (pinfunction "+INB_15") (pintype "input"))
      (node (ref "J5") (pin "1") (pinfunction "1_1") (pintype "passive"))
      (node (ref "P2") (pin "7") (pinfunction "7_7") (pintype "passive"))
      (node (ref "R28") (pin "2") (pinfunction "2_2") (pintype "passive"))
    )
    (net (code "23") (name "Net-(IC2--INA)") (class "Default")
      (node (ref "IC2") (pin "1") (pinfunction "-INA_1") (pintype "input"))
      (node (ref "J3") (pin "2") (pinfunction "2_2") (pintype "passive"))
      (node (ref "P2") (pin "6") (pinfunction "6_6") (pintype "passive"))
      (node (ref "R26") (pin "1") (pinfunction "1_1") (pintype "passive"))
    )
    (net (code "24") (name "Net-(IC2--INB)") (class "Default")
      (node (ref "IC2") (pin "16") (pinfunction "-INB_16") (pintype "input"))
      (node (ref "J5") (pin "2") (pinfunction "2_2") (pintype "passive"))
      (node (ref "P2") (pin "8") (pinfunction "8_8") (pintype "passive"))
      (node (ref "R31") (pin "1") (pinfunction "1_1") (pintype "passive"))
    )
    (net (code "25") (name "Net-(IC2-OUTA)") (class "Default")
      (node (ref "IC2") (pin "6") (pinfunction "OUTA_6") (pintype "output"))
      (node (ref "IC2") (pin "7") (pinfunction "SENSEA_7") (pintype "passive"))
      (node (ref "OP1") (pin "12") (pinfunction "+IN3_12") (pintype "passive"))
    )
    (net (code "26") (name "Net-(IC2-OUTB)") (class "Default")
      (node (ref "IC2") (pin "10") (pinfunction "SENSEB_10") (pintype "passive"))
      (node (ref "IC2") (pin "11") (pinfunction "OUTB_11") (pintype "output"))
      (node (ref "OP1") (pin "10") (pinfunction "+IN4_10") (pintype "passive"))
    )
    (net (code "27") (name "Net-(IC2-RGA)") (class "Default")
      (node (ref "IC2") (pin "3") (pinfunction "RGA_3") (pintype "passive"))
      (node (ref "R22") (pin "3") (pinfunction "3_3") (pintype "passive"))
    )
    (net (code "28") (name "Net-(IC2-RGA@1)") (class "Default")
      (node (ref "IC2") (pin "4") (pinfunction "RGA@1_4") (pintype "passive"))
      (node (ref "P4") (pin "1") (pinfunction "1_1") (pintype "passive"))
    )
    (net (code "29") (name "Net-(IC2-RGB)") (class "Default")
      (node (ref "IC2") (pin "14") (pinfunction "RGB_14") (pintype "passive"))
      (node (ref "R27") (pin "3") (pinfunction "3_3") (pintype "passive"))
    )
    (net (code "30") (name "Net-(IC2-RGB@1)") (class "Default")
      (node (ref "IC2") (pin "13") (pinfunction "RGB@1_13") (pintype "passive"))
      (node (ref "P9") (pin "1") (pinfunction "1_1") (pintype "passive"))
    )
    (net (code "31") (name "Net-(OP1--IN1)") (class "Default")
      (node (ref "OP1") (pin "2") (pinfunction "-IN1_2") (pintype "passive"))
      (node (ref "R17") (pin "1") (pinfunction "1_1") (pintype "passive"))
      (node (ref "R4") (pin "1") (pinfunction "1_1") (pintype "passive"))
    )
    (net (code "32") (name "Net-(OP1--IN2)") (class "Default")
      (node (ref "OP1") (pin "6") (pinfunction "-IN2_6") (pintype "passive"))
      (node (ref "R11") (pin "1") (pinfunction "1_1") (pintype "passive"))
      (node (ref "R14") (pin "1") (pinfunction "1_1") (pintype "passive"))
    )
    (net (code "33") (name "Net-(OP1--IN3)") (class "Default")
      (node (ref "OP1") (pin "13") (pinfunction "-IN3_13") (pintype "passive"))
      (node (ref "R21") (pin "1") (pinfunction "1_1") (pintype "passive"))
      (node (ref "R24") (pin "1") (pinfunction "1_1") (pintype "passive"))
    )
    (net (code "34") (name "Net-(OP1--IN4)") (class "Default")
      (node (ref "OP1") (pin "9") (pinfunction "-IN4_9") (pintype "passive"))
      (node (ref "R19") (pin "1") (pinfunction "1_1") (pintype "passive"))
      (node (ref "R29") (pin "1") (pinfunction "1_1") (pintype "passive"))
    )
    (net (code "35") (name "Net-(OP1-OUT1)") (class "Default")
      (node (ref "C1") (pin "1") (pinfunction "1_1") (pintype "passive"))
      (node (ref "OP1") (pin "1") (pinfunction "OUT1_1") (pintype "passive"))
      (node (ref "R4") (pin "2") (pinfunction "2_2") (pintype "passive"))
      (node (ref "R4") (pin "3") (pinfunction "3_3") (pintype "passive"))
    )
    (net (code "36") (name "Net-(OP1-OUT2)") (class "Default")
      (node (ref "C5") (pin "1") (pinfunction "1_1") (pintype "passive"))
      (node (ref "OP1") (pin "7") (pinfunction "OUT2_7") (pintype "passive"))
      (node (ref "R11") (pin "2") (pinfunction "2_2") (pintype "passive"))
      (node (ref "R11") (pin "3") (pinfunction "3_3") (pintype "passive"))
    )
    (net (code "37") (name "Net-(OP1-OUT3)") (class "Default")
      (node (ref "C13") (pin "1") (pinfunction "1_1") (pintype "passive"))
      (node (ref "OP1") (pin "14") (pinfunction "OUT3_14") (pintype "passive"))
      (node (ref "R24") (pin "2") (pinfunction "2_2") (pintype "passive"))
      (node (ref "R24") (pin "3") (pinfunction "3_3") (pintype "passive"))
    )
    (net (code "38") (name "Net-(OP1-OUT4)") (class "Default")
      (node (ref "C14") (pin "1") (pinfunction "1_1") (pintype "passive"))
      (node (ref "OP1") (pin "8") (pinfunction "OUT4_8") (pintype "passive"))
      (node (ref "R29") (pin "2") (pinfunction "2_2") (pintype "passive"))
      (node (ref "R29") (pin "3") (pinfunction "3_3") (pintype "passive"))
    )
    (net (code "39") (name "Net-(P1-Pad2)") (class "Default")
      (node (ref "P1") (pin "2") (pinfunction "2_2") (pintype "passive"))
      (node (ref "R3") (pin "1") (pinfunction "1_1") (pintype "passive"))
      (node (ref "R3") (pin "2") (pinfunction "2_2") (pintype "passive"))
    )
    (net (code "40") (name "Net-(P3-Pad2)") (class "Default")
      (node (ref "P3") (pin "2") (pinfunction "2_2") (pintype "passive"))
      (node (ref "R9") (pin "1") (pinfunction "1_1") (pintype "passive"))
      (node (ref "R9") (pin "2") (pinfunction "2_2") (pintype "passive"))
    )
    (net (code "41") (name "Net-(P4-Pad2)") (class "Default")
      (node (ref "P4") (pin "2") (pinfunction "2_2") (pintype "passive"))
      (node (ref "R22") (pin "1") (pinfunction "1_1") (pintype "passive"))
      (node (ref "R22") (pin "2") (pinfunction "2_2") (pintype "passive"))
    )
    (net (code "42") (name "Net-(P9-Pad2)") (class "Default")
      (node (ref "P9") (pin "2") (pinfunction "2_2") (pintype "passive"))
      (node (ref "R27") (pin "1") (pinfunction "1_1") (pintype "passive"))
      (node (ref "R27") (pin "2") (pinfunction "2_2") (pintype "passive"))
    )
    (net (code "43") (name "Net-(U1-FB)") (class "Default")
      (node (ref "C4") (pin "2") (pinfunction "2_2") (pintype "passive"))
      (node (ref "R1") (pin "1") (pinfunction "1_1") (pintype "passive"))
      (node (ref "R7") (pin "2") (pinfunction "2_2") (pintype "passive"))
      (node (ref "U1") (pin "4") (pinfunction "FB_4") (pintype "input"))
    )
    (net (code "44") (name "Net-(U2-FB)") (class "Default")
      (node (ref "C9") (pin "1") (pinfunction "1_1") (pintype "passive"))
      (node (ref "R15") (pin "1") (pinfunction "1_1") (pintype "passive"))
      (node (ref "R18") (pin "2") (pinfunction "2_2") (pintype "passive"))
      (node (ref "U2") (pin "4") (pinfunction "FB_4") (pintype "input"))
    )
    (net (code "45") (name "Vbat+") (class "Default")
      (node (ref "C2") (pin "1") (pinfunction "1_1") (pintype "passive"))
      (node (ref "C8") (pin "1") (pinfunction "1_1") (pintype "passive"))
      (node (ref "J4") (pin "1") (pinfunction "1_1") (pintype "passive"))
      (node (ref "U1") (pin "7") (pinfunction "VIN_7") (pintype "input"))
      (node (ref "U2") (pin "7") (pinfunction "VIN_7") (pintype "input"))
    )
    (net (code "46") (name "unconnected-(P5-Pad1)") (class "Default")
      (node (ref "P5") (pin "1") (pinfunction "1_1") (pintype "passive"))
    )
    (net (code "47") (name "unconnected-(P5-Pad2)") (class "Default")
      (node (ref "P5") (pin "2") (pinfunction "2_2") (pintype "passive"))
    )
    (net (code "48") (name "unconnected-(P5-Pad3)") (class "Default")
      (node (ref "P5") (pin "3") (pinfunction "3_3") (pintype "passive"))
    )
    (net (code "49") (name "unconnected-(P5-Pad4)") (class "Default")
      (node (ref "P5") (pin "4") (pinfunction "4_4") (pintype "passive"))
    )
    (net (code "50") (name "unconnected-(P5-Pad5)") (class "Default")
      (node (ref "P5") (pin "5") (pinfunction "5_5") (pintype "passive"))
    )
    (net (code "51") (name "unconnected-(P5-Pad6)") (class "Default")
      (node (ref "P5") (pin "6") (pinfunction "6_6") (pintype "passive"))
    )
    (net (code "52") (name "unconnected-(P5-Pad7)") (class "Default")
      (node (ref "P5") (pin "7") (pinfunction "7_7") (pintype "passive"))
    )
    (net (code "53") (name "unconnected-(P5-Pad8)") (class "Default")
      (node (ref "P5") (pin "8") (pinfunction "8_8") (pintype "passive"))
    )
    (net (code "54") (name "unconnected-(P5-Pad9)") (class "Default")
      (node (ref "P5") (pin "9") (pinfunction "9_9") (pintype "passive"))
    )
    (net (code "55") (name "unconnected-(P5-Pad10)") (class "Default")
      (node (ref "P5") (pin "10") (pinfunction "10_10") (pintype "passive"))
    )
    (net (code "56") (name "unconnected-(P5-Pad11)") (class "Default")
      (node (ref "P5") (pin "11") (pinfunction "11_11") (pintype "passive"))
    )
    (net (code "57") (name "unconnected-(P5-Pad12)") (class "Default")
      (node (ref "P5") (pin "12") (pinfunction "12_12") (pintype "passive"))
    )
    (net (code "58") (name "unconnected-(P5-Pad13)") (class "Default")
      (node (ref "P5") (pin "13") (pinfunction "13_13") (pintype "passive"))
    )
    (net (code "59") (name "unconnected-(P5-Pad14)") (class "Default")
      (node (ref "P5") (pin "14") (pinfunction "14_14") (pintype "passive"))
    )
    (net (code "60") (name "unconnected-(P5-Pad15)") (class "Default")
      (node (ref "P5") (pin "15") (pinfunction "15_15") (pintype "passive"))
    )
    (net (code "61") (name "unconnected-(P5-Pad16)") (class "Default")
      (node (ref "P5") (pin "16") (pinfunction "16_16") (pintype "passive"))
    )
    (net (code "62") (name "unconnected-(P5-Pad17)") (class "Default")
      (node (ref "P5") (pin "17") (pinfunction "17_17") (pintype "passive"))
    )
    (net (code "63") (name "unconnected-(P5-Pad18)") (class "Default")
      (node (ref "P5") (pin "18") (pinfunction "18_18") (pintype "passive"))
    )
    (net (code "64") (name "unconnected-(P5-Pad19)") (class "Default")
      (node (ref "P5") (pin "19") (pinfunction "19_19") (pintype "passive"))
    )
    (net (code "65") (name "unconnected-(P5-Pad20)") (class "Default")
      (node (ref "P5") (pin "20") (pinfunction "20_20") (pintype "passive"))
    )
    (net (code "66") (name "unconnected-(P6-Pad1)") (class "Default")
      (node (ref "P6") (pin "1") (pinfunction "1_1") (pintype "passive"))
    )
    (net (code "67") (name "unconnected-(P6-Pad2)") (class "Default")
      (node (ref "P6") (pin "2") (pinfunction "2_2") (pintype "passive"))
    )
    (net (code "68") (name "unconnected-(P6-Pad3)") (class "Default")
      (node (ref "P6") (pin "3") (pinfunction "3_3") (pintype "passive"))
    )
    (net (code "69") (name "unconnected-(P6-Pad4)") (class "Default")
      (node (ref "P6") (pin "4") (pinfunction "4_4") (pintype "passive"))
    )
    (net (code "70") (name "unconnected-(P6-Pad5)") (class "Default")
      (node (ref "P6") (pin "5") (pinfunction "5_5") (pintype "passive"))
    )
    (net (code "71") (name "unconnected-(P6-Pad6)") (class "Default")
      (node (ref "P6") (pin "6") (pinfunction "6_6") (pintype "passive"))
    )
    (net (code "72") (name "unconnected-(P6-Pad8)") (class "Default")
      (node (ref "P6") (pin "8") (pinfunction "8_8") (pintype "passive"))
    )
    (net (code "73") (name "unconnected-(P6-Pad9)") (class "Default")
      (node (ref "P6") (pin "9") (pinfunction "9_9") (pintype "passive"))
    )
    (net (code "74") (name "unconnected-(P6-Pad10)") (class "Default")
      (node (ref "P6") (pin "10") (pinfunction "10_10") (pintype "passive"))
    )
    (net (code "75") (name "unconnected-(P6-Pad12)") (class "Default")
      (node (ref "P6") (pin "12") (pinfunction "12_12") (pintype "passive"))
    )
    (net (code "76") (name "unconnected-(P6-Pad14)") (class "Default")
      (node (ref "P6") (pin "14") (pinfunction "14_14") (pintype "passive"))
    )
    (net (code "77") (name "unconnected-(P6-Pad16)") (class "Default")
      (node (ref "P6") (pin "16") (pinfunction "16_16") (pintype "passive"))
    )
    (net (code "78") (name "unconnected-(P7-Pad2)") (class "Default")
      (node (ref "P7") (pin "2") (pinfunction "2_2") (pintype "passive"))
    )
    (net (code "79") (name "unconnected-(P7-Pad4)") (class "Default")
      (node (ref "P7") (pin "4") (pinfunction "4_4") (pintype "passive"))
    )
    (net (code "80") (name "unconnected-(P7-Pad6)") (class "Default")
      (node (ref "P7") (pin "6") (pinfunction "6_6") (pintype "passive"))
    )
    (net (code "81") (name "unconnected-(P7-Pad8)") (class "Default")
      (node (ref "P7") (pin "8") (pinfunction "8_8") (pintype "passive"))
    )
    (net (code "82") (name "unconnected-(P7-Pad9)") (class "Default")
      (node (ref "P7") (pin "9") (pinfunction "9_9") (pintype "passive"))
    )
    (net (code "83") (name "unconnected-(P7-Pad10)") (class "Default")
      (node (ref "P7") (pin "10") (pinfunction "10_10") (pintype "passive"))
    )
    (net (code "84") (name "unconnected-(P7-Pad11)") (class "Default")
      (node (ref "P7") (pin "11") (pinfunction "11_11") (pintype "passive"))
    )
    (net (code "85") (name "unconnected-(P7-Pad12)") (class "Default")
      (node (ref "P7") (pin "12") (pinfunction "12_12") (pintype "passive"))
    )
    (net (code "86") (name "unconnected-(P7-Pad13)") (class "Default")
      (node (ref "P7") (pin "13") (pinfunction "13_13") (pintype "passive"))
    )
    (net (code "87") (name "unconnected-(P7-Pad14)") (class "Default")
      (node (ref "P7") (pin "14") (pinfunction "14_14") (pintype "passive"))
    )
    (net (code "88") (name "unconnected-(P7-Pad15)") (class "Default")
      (node (ref "P7") (pin "15") (pinfunction "15_15") (pintype "passive"))
    )
    (net (code "89") (name "unconnected-(P7-Pad16)") (class "Default")
      (node (ref "P7") (pin "16") (pinfunction "16_16") (pintype "passive"))
    )
    (net (code "90") (name "unconnected-(P7-Pad17)") (class "Default")
      (node (ref "P7") (pin "17") (pinfunction "17_17") (pintype "passive"))
    )
    (net (code "91") (name "unconnected-(P7-Pad18)") (class "Default")
      (node (ref "P7") (pin "18") (pinfunction "18_18") (pintype "passive"))
    )
    (net (code "92") (name "unconnected-(P7-Pad19)") (class "Default")
      (node (ref "P7") (pin "19") (pinfunction "19_19") (pintype "passive"))
    )
    (net (code "93") (name "unconnected-(P7-Pad20)") (class "Default")
      (node (ref "P7") (pin "20") (pinfunction "20_20") (pintype "passive"))
    )
    (net (code "94") (name "unconnected-(P7-Pad21)") (class "Default")
      (node (ref "P7") (pin "21") (pinfunction "21_21") (pintype "passive"))
    )
    (net (code "95") (name "unconnected-(P7-Pad22)") (class "Default")
      (node (ref "P7") (pin "22") (pinfunction "22_22") (pintype "passive"))
    )
    (net (code "96") (name "unconnected-(P7-Pad23)") (class "Default")
      (node (ref "P7") (pin "23") (pinfunction "23_23") (pintype "passive"))
    )
    (net (code "97") (name "unconnected-(P7-Pad24)") (class "Default")
      (node (ref "P7") (pin "24") (pinfunction "24_24") (pintype "passive"))
    )
    (net (code "98") (name "unconnected-(P7-Pad25)") (class "Default")
      (node (ref "P7") (pin "25") (pinfunction "25_25") (pintype "passive"))
    )
    (net (code "99") (name "unconnected-(P7-Pad26)") (class "Default")
      (node (ref "P7") (pin "26") (pinfunction "26_26") (pintype "passive"))
    )
    (net (code "100") (name "unconnected-(P7-Pad27)") (class "Default")
      (node (ref "P7") (pin "27") (pinfunction "27_27") (pintype "passive"))
    )
    (net (code "101") (name "unconnected-(P7-Pad28)") (class "Default")
      (node (ref "P7") (pin "28") (pinfunction "28_28") (pintype "passive"))
    )
    (net (code "102") (name "unconnected-(P7-Pad29)") (class "Default")
      (node (ref "P7") (pin "29") (pinfunction "29_29") (pintype "passive"))
    )
    (net (code "103") (name "unconnected-(P7-Pad30)") (class "Default")
      (node (ref "P7") (pin "30") (pinfunction "30_30") (pintype "passive"))
    )
    (net (code "104") (name "unconnected-(P8-Pad1)") (class "Default")
      (node (ref "P8") (pin "1") (pinfunction "1_1") (pintype "passive"))
    )
    (net (code "105") (name "unconnected-(P8-Pad2)") (class "Default")
      (node (ref "P8") (pin "2") (pinfunction "2_2") (pintype "passive"))
    )
    (net (code "106") (name "unconnected-(P8-Pad3)") (class "Default")
      (node (ref "P8") (pin "3") (pinfunction "3_3") (pintype "passive"))
    )
    (net (code "107") (name "unconnected-(P8-Pad4)") (class "Default")
      (node (ref "P8") (pin "4") (pinfunction "4_4") (pintype "passive"))
    )
    (net (code "108") (name "unconnected-(P8-Pad5)") (class "Default")
      (node (ref "P8") (pin "5") (pinfunction "5_5") (pintype "passive"))
    )
    (net (code "109") (name "unconnected-(P8-Pad6)") (class "Default")
      (node (ref "P8") (pin "6") (pinfunction "6_6") (pintype "passive"))
    )
    (net (code "110") (name "unconnected-(P8-Pad7)") (class "Default")
      (node (ref "P8") (pin "7") (pinfunction "7_7") (pintype "passive"))
    )
    (net (code "111") (name "unconnected-(P8-Pad8)") (class "Default")
      (node (ref "P8") (pin "8") (pinfunction "8_8") (pintype "passive"))
    )
    (net (code "112") (name "unconnected-(P8-Pad9)") (class "Default")
      (node (ref "P8") (pin "9") (pinfunction "9_9") (pintype "passive"))
    )
    (net (code "113") (name "unconnected-(P8-Pad10)") (class "Default")
      (node (ref "P8") (pin "10") (pinfunction "10_10") (pintype "passive"))
    )
    (net (code "114") (name "unconnected-(P8-Pad11)") (class "Default")
      (node (ref "P8") (pin "11") (pinfunction "11_11") (pintype "passive"))
    )
    (net (code "115") (name "unconnected-(P8-Pad12)") (class "Default")
      (node (ref "P8") (pin "12") (pinfunction "12_12") (pintype "passive"))
    )
    (net (code "116") (name "unconnected-(P8-Pad13)") (class "Default")
      (node (ref "P8") (pin "13") (pinfunction "13_13") (pintype "passive"))
    )
    (net (code "117") (name "unconnected-(P8-Pad14)") (class "Default")
      (node (ref "P8") (pin "14") (pinfunction "14_14") (pintype "passive"))
    )
    (net (code "118") (name "unconnected-(P8-Pad15)") (class "Default")
      (node (ref "P8") (pin "15") (pinfunction "15_15") (pintype "passive"))
    )
    (net (code "119") (name "unconnected-(P8-Pad16)") (class "Default")
      (node (ref "P8") (pin "16") (pinfunction "16_16") (pintype "passive"))
    )
    (net (code "120") (name "unconnected-(P8-Pad17)") (class "Default")
      (node (ref "P8") (pin "17") (pinfunction "17_17") (pintype "passive"))
    )
    (net (code "121") (name "unconnected-(P8-Pad18)") (class "Default")
      (node (ref "P8") (pin "18") (pinfunction "18_18") (pintype "passive"))
    )
    (net (code "122") (name "unconnected-(P8-Pad19)") (class "Default")
      (node (ref "P8") (pin "19") (pinfunction "19_19") (pintype "passive"))
    )
    (net (code "123") (name "unconnected-(P8-Pad20)") (class "Default")
      (node (ref "P8") (pin "20") (pinfunction "20_20") (pintype "passive"))
    )
    (net (code "124") (name "unconnected-(P8-Pad21)") (class "Default")
      (node (ref "P8") (pin "21") (pinfunction "21_21") (pintype "passive"))
    )
    (net (code "125") (name "unconnected-(P8-Pad22)") (class "Default")
      (node (ref "P8") (pin "22") (pinfunction "22_22") (pintype "passive"))
    )
    (net (code "126") (name "unconnected-(P8-Pad23)") (class "Default")
      (node (ref "P8") (pin "23") (pinfunction "23_23") (pintype "passive"))
    )
    (net (code "127") (name "unconnected-(P8-Pad24)") (class "Default")
      (node (ref "P8") (pin "24") (pinfunction "24_24") (pintype "passive"))
    )
    (net (code "128") (name "unconnected-(P8-Pad25)") (class "Default")
      (node (ref "P8") (pin "25") (pinfunction "25_25") (pintype "passive"))
    )
    (net (code "129") (name "unconnected-(P8-Pad26)") (class "Default")
      (node (ref "P8") (pin "26") (pinfunction "26_26") (pintype "passive"))
    )
    (net (code "130") (name "unconnected-(P8-Pad27)") (class "Default")
      (node (ref "P8") (pin "27") (pinfunction "27_27") (pintype "passive"))
    )
    (net (code "131") (name "unconnected-(P8-Pad28)") (class "Default")
      (node (ref "P8") (pin "28") (pinfunction "28_28") (pintype "passive"))
    )
    (net (code "132") (name "unconnected-(P8-Pad29)") (class "Default")
      (node (ref "P8") (pin "29") (pinfunction "29_29") (pintype "passive"))
    )
    (net (code "133") (name "unconnected-(P8-Pad30)") (class "Default")
      (node (ref "P8") (pin "30") (pinfunction "30_30") (pintype "passive"))
    )
    (net (code "134") (name "unconnected-(P8-Pad31)") (class "Default")
      (node (ref "P8") (pin "31") (pinfunction "31_31") (pintype "passive"))
    )
    (net (code "135") (name "unconnected-(P8-Pad32)") (class "Default")
      (node (ref "P8") (pin "32") (pinfunction "32_32") (pintype "passive"))
    )
    (net (code "136") (name "unconnected-(P8-Pad33)") (class "Default")
      (node (ref "P8") (pin "33") (pinfunction "33_33") (pintype "passive"))
    )
    (net (code "137") (name "unconnected-(P8-Pad34)") (class "Default")
      (node (ref "P8") (pin "34") (pinfunction "34_34") (pintype "passive"))
    )
  )
)
